# Zio_Qwiic_LoRa_Module_915MHZ.net
KiCad netlist of a schematic drawn in EAGLE
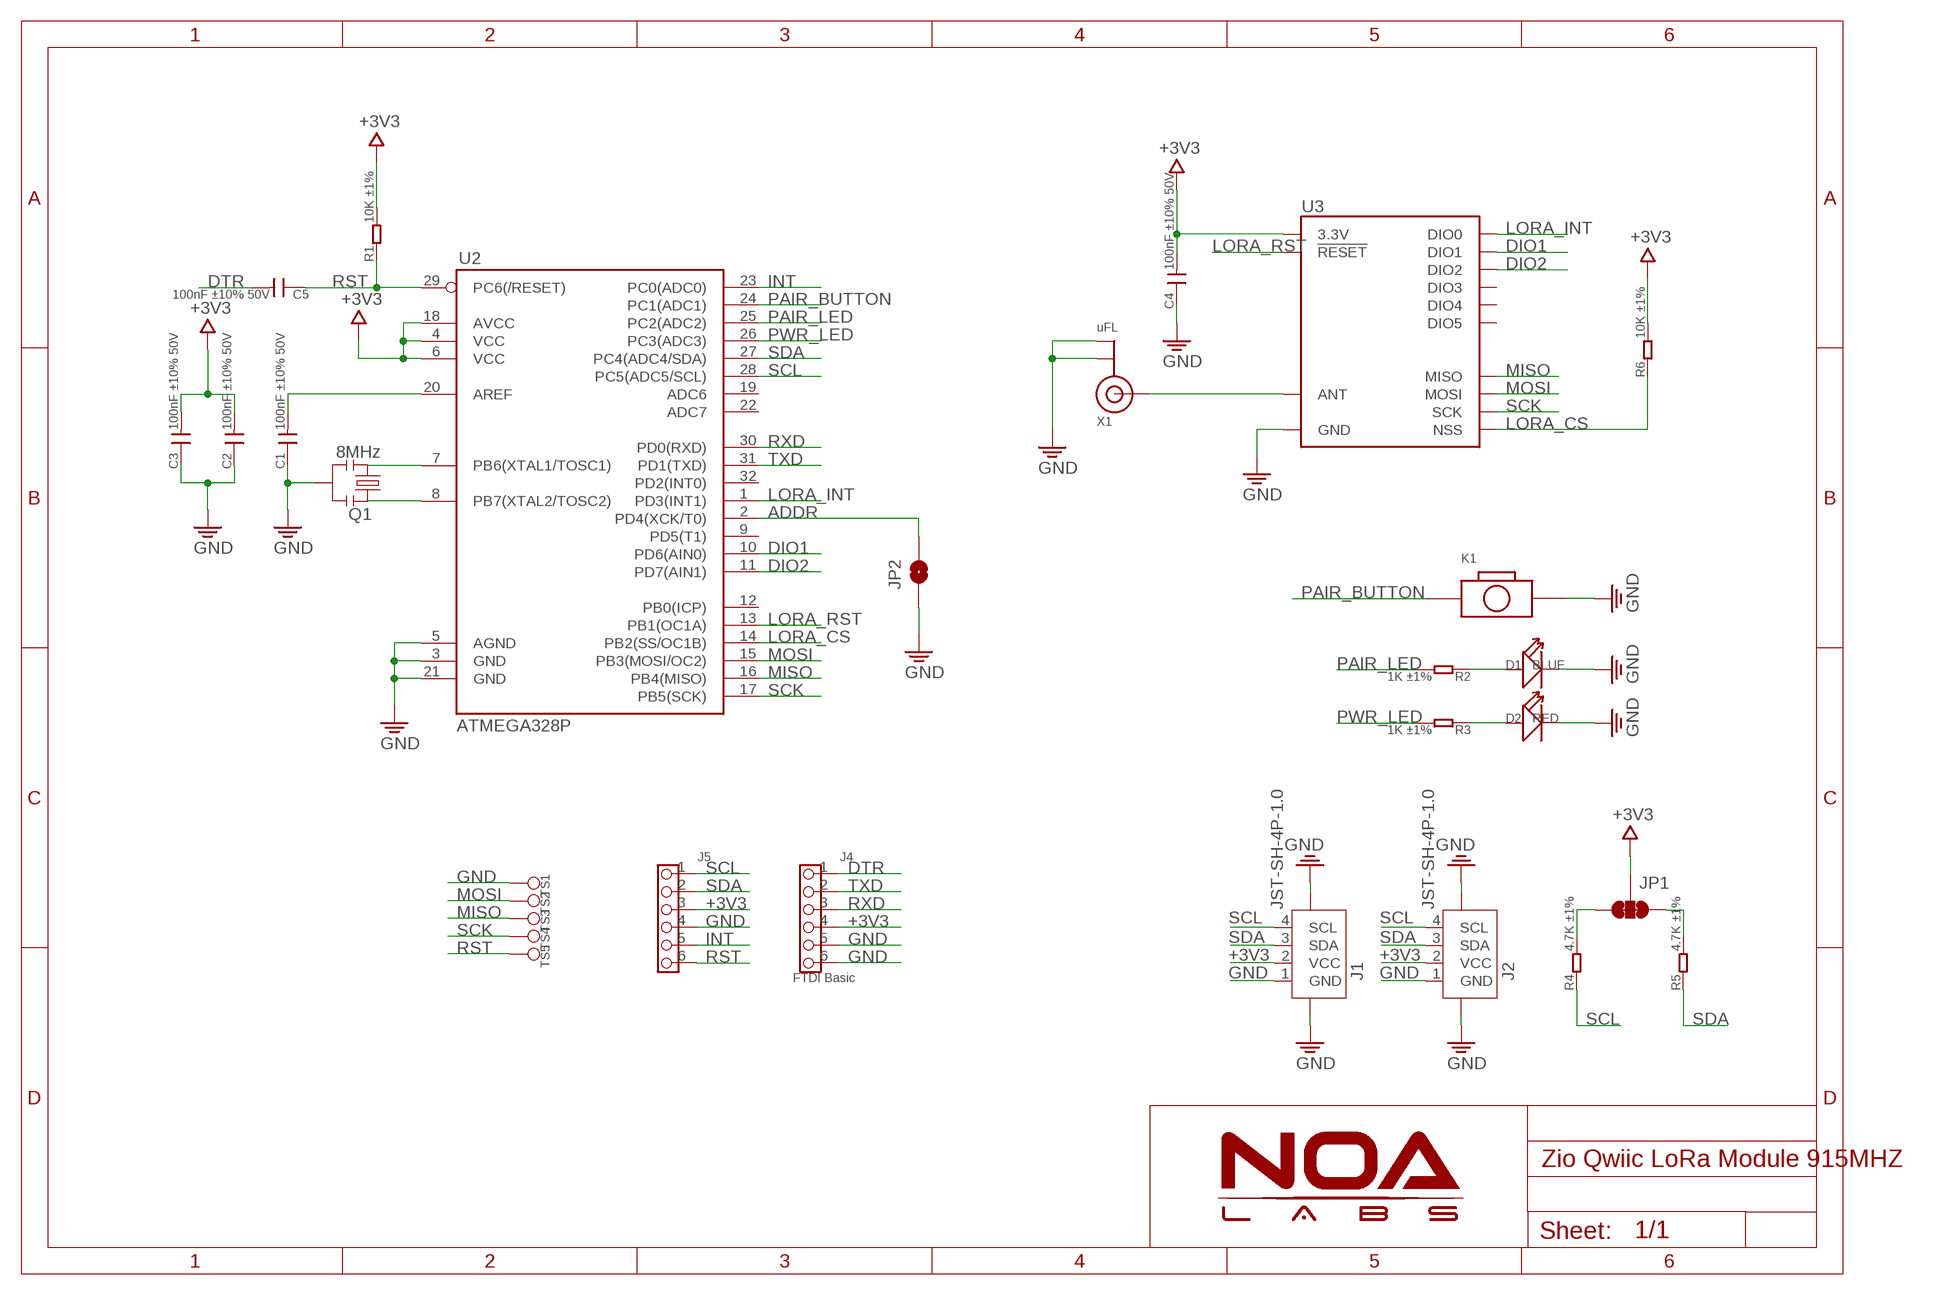
[diagram p0: schematic, sheet 1]

(export (version "E")
  (design (tool "Eeschema 10.0.6"))
  (components
    (comp (ref "C1")
      (value "100nF ±10% 50V")
      (footprint "eagle-import:C0603")
      (libsource (lib "eagle-import") (part "C-0603"))
    )
    (comp (ref "C2")
      (value "100nF ±10% 50V")
      (footprint "eagle-import:C0603")
      (libsource (lib "eagle-import") (part "C-0603"))
    )
    (comp (ref "C3")
      (value "100nF ±10% 50V")
      (footprint "eagle-import:C0603")
      (libsource (lib "eagle-import") (part "C-0603"))
    )
    (comp (ref "C4")
      (value "100nF ±10% 50V")
      (footprint "eagle-import:C0603")
      (libsource (lib "eagle-import") (part "C-0603"))
    )
    (comp (ref "C5")
      (value "100nF ±10% 50V")
      (footprint "eagle-import:C0603")
      (libsource (lib "eagle-import") (part "C-0603"))
    )
    (comp (ref "D1")
      (value "BLUE")
      (footprint "eagle-import:LED-0603")
      (libsource (lib "eagle-import") (part "LED'0603'"))
    )
    (comp (ref "D2")
      (value "RED")
      (footprint "eagle-import:LED-0603")
      (libsource (lib "eagle-import") (part "LED'0603'"))
    )
    (comp (ref "J1")
      (value "JST-SH-4P-1.0")
      (footprint "eagle-import:JST-SH-4P")
      (libsource (lib "eagle-import") (part "JST-SH-4P-1.0"))
    )
    (comp (ref "J2")
      (value "JST-SH-4P-1.0")
      (footprint "eagle-import:JST-SH-4P")
      (libsource (lib "eagle-import") (part "JST-SH-4P-1.0"))
    )
    (comp (ref "J4")
      (value "FTDI Basic")
      (footprint "eagle-import:6P-2.54-60_35MIL")
      (libsource (lib "eagle-import") (part "HEADER-6P-60/35MIL"))
    )
    (comp (ref "J5")
      (value "HEADER-6P-60/35MIL")
      (footprint "eagle-import:6P-2.54-60_35MIL")
      (libsource (lib "eagle-import") (part "HEADER-6P-60/35MIL"))
    )
    (comp (ref "JP1")
      (value "SMT-JUMPER_3_2-NC_TRACE")
      (footprint "eagle-import:SMT-JUMPER_3_2-NC_TRACE")
      (libsource (lib "eagle-import") (part "SMT-JUMPER_3_2-NC_TRACE"))
    )
    (comp (ref "JP2")
      (value "JUMPER-SMT_2_NC_PASTE_NOCREM")
      (footprint "eagle-import:SMT-JUMPER_2_NC_PASTE_SILK_NOCREM")
      (libsource (lib "eagle-import") (part "JUMPER-SMT_2_NC_PASTE_NOCREM"))
    )
    (comp (ref "K1")
      (value "BOTTON-2PSKRKAEE020")
      (footprint "eagle-import:SKRKAEE020")
      (libsource (lib "eagle-import") (part "BOTTON-2PSKRKAEE020"))
    )
    (comp (ref "Q1")
      (value "8MHz")
      (footprint "eagle-import:RESONATOR-SMD")
      (libsource (lib "eagle-import") (part "RESONATORSMD"))
    )
    (comp (ref "R1")
      (value "10K ±1%")
      (footprint "eagle-import:R0603")
      (libsource (lib "eagle-import") (part "R-0603"))
    )
    (comp (ref "R2")
      (value "1K ±1%")
      (footprint "eagle-import:R0603")
      (libsource (lib "eagle-import") (part "R-0603"))
    )
    (comp (ref "R3")
      (value "1K ±1%")
      (footprint "eagle-import:R0603")
      (libsource (lib "eagle-import") (part "R-0603"))
    )
    (comp (ref "R4")
      (value "4.7K ±1%")
      (footprint "eagle-import:R0603")
      (libsource (lib "eagle-import") (part "R-0603"))
    )
    (comp (ref "R5")
      (value "4.7K ±1%")
      (footprint "eagle-import:R0603")
      (libsource (lib "eagle-import") (part "R-0603"))
    )
    (comp (ref "R6")
      (value "10K ±1%")
      (footprint "eagle-import:R0603")
      (libsource (lib "eagle-import") (part "R-0603"))
    )
    (comp (ref "TS1")
      (value "TEST_POINT35MIL")
      (footprint "eagle-import:1P-35MIL")
      (libsource (lib "eagle-import") (part "TEST_POINT35MIL"))
    )
    (comp (ref "TS2")
      (value "TEST_POINT35MIL")
      (footprint "eagle-import:1P-35MIL")
      (libsource (lib "eagle-import") (part "TEST_POINT35MIL"))
    )
    (comp (ref "TS3")
      (value "TEST_POINT35MIL")
      (footprint "eagle-import:1P-35MIL")
      (libsource (lib "eagle-import") (part "TEST_POINT35MIL"))
    )
    (comp (ref "TS4")
      (value "TEST_POINT35MIL")
      (footprint "eagle-import:1P-35MIL")
      (libsource (lib "eagle-import") (part "TEST_POINT35MIL"))
    )
    (comp (ref "TS5")
      (value "TEST_POINT35MIL")
      (footprint "eagle-import:1P-35MIL")
      (libsource (lib "eagle-import") (part "TEST_POINT35MIL"))
    )
    (comp (ref "U2")
      (value "ATMEGA328P")
      (footprint "eagle-import:TQFP32-08")
      (libsource (lib "eagle-import") (part "ATMEGA168"))
    )
    (comp (ref "U3")
      (value "SPARKX_RFM96W")
      (footprint "eagle-import:SPARKX_RFM95_96_97_98W")
      (libsource (lib "eagle-import") (part "SPARKX_RFM96W"))
    )
    (comp (ref "X1")
      (value "uFL")
      (footprint "eagle-import:U.FL")
      (libsource (lib "eagle-import") (part "ANTENNA_U.FL"))
    )
  )
  (nets
    (net (code "1") (name "+3V3") (class "Default")
      (node (ref "C2") (pin "2") (pinfunction "2_2") (pintype "passive"))
      (node (ref "C3") (pin "2") (pinfunction "2_2") (pintype "passive"))
      (node (ref "C4") (pin "2") (pinfunction "2_2") (pintype "passive"))
      (node (ref "J1") (pin "2") (pinfunction "VCC_2") (pintype "bidirectional"))
      (node (ref "J2") (pin "2") (pinfunction "VCC_2") (pintype "bidirectional"))
      (node (ref "J4") (pin "4") (pinfunction "4_4") (pintype "bidirectional"))
      (node (ref "J5") (pin "3") (pinfunction "3_3") (pintype "bidirectional"))
      (node (ref "JP1") (pin "2") (pinfunction "2_2") (pintype "passive"))
      (node (ref "R1") (pin "2") (pinfunction "2_2") (pintype "passive"))
      (node (ref "R6") (pin "2") (pinfunction "2_2") (pintype "passive"))
      (node (ref "U2") (pin "18") (pinfunction "AVCC_18") (pintype "bidirectional"))
      (node (ref "U2") (pin "4") (pinfunction "VCC_4") (pintype "bidirectional"))
      (node (ref "U2") (pin "6") (pinfunction "VCC_6") (pintype "bidirectional"))
      (node (ref "U3") (pin "3.3V") (pinfunction "3.3V_3.3V") (pintype "bidirectional"))
    )
    (net (code "2") (name "/ADDR") (class "Default")
      (node (ref "JP2") (pin "2") (pinfunction "2_2") (pintype "passive"))
      (node (ref "U2") (pin "2") (pinfunction "PD4(XCK/T0)_2") (pintype "bidirectional"))
    )
    (net (code "3") (name "/DIO1") (class "Default")
      (node (ref "U2") (pin "10") (pinfunction "PD6(AIN0)_10") (pintype "bidirectional"))
      (node (ref "U3") (pin "DIO1") (pinfunction "DIO1_DIO1") (pintype "bidirectional"))
    )
    (net (code "4") (name "/DIO2") (class "Default")
      (node (ref "U2") (pin "11") (pinfunction "PD7(AIN1)_11") (pintype "bidirectional"))
      (node (ref "U3") (pin "DIO2") (pinfunction "DIO2_DIO2") (pintype "bidirectional"))
    )
    (net (code "5") (name "/DTR") (class "Default")
      (node (ref "C5") (pin "2") (pinfunction "2_2") (pintype "passive"))
      (node (ref "J4") (pin "1") (pinfunction "1_1") (pintype "bidirectional"))
    )
    (net (code "6") (name "/INT") (class "Default")
      (node (ref "J5") (pin "5") (pinfunction "5_5") (pintype "bidirectional"))
      (node (ref "U2") (pin "23") (pinfunction "PC0(ADC0)_23") (pintype "bidirectional"))
    )
    (net (code "7") (name "/LORA_CS") (class "Default")
      (node (ref "R6") (pin "1") (pinfunction "1_1") (pintype "passive"))
      (node (ref "U2") (pin "14") (pinfunction "PB2(SS/OC1B)_14") (pintype "bidirectional"))
      (node (ref "U3") (pin "NSS") (pinfunction "NSS_NSS") (pintype "bidirectional"))
    )
    (net (code "8") (name "/LORA_INT") (class "Default")
      (node (ref "U2") (pin "1") (pinfunction "PD3(INT1)_1") (pintype "bidirectional"))
      (node (ref "U3") (pin "DIO0") (pinfunction "DIO0_DIO0") (pintype "bidirectional"))
    )
    (net (code "9") (name "/LORA_RST") (class "Default")
      (node (ref "U2") (pin "13") (pinfunction "PB1(OC1A)_13") (pintype "bidirectional"))
      (node (ref "U3") (pin "!RESET") (pinfunction "~{RESET}_!RESET") (pintype "bidirectional"))
    )
    (net (code "10") (name "/MISO") (class "Default")
      (node (ref "TS3") (pin "P$1") (pinfunction "1_P$1") (pintype "bidirectional"))
      (node (ref "U2") (pin "16") (pinfunction "PB4(MISO)_16") (pintype "bidirectional"))
      (node (ref "U3") (pin "MISO") (pinfunction "MISO_MISO") (pintype "bidirectional"))
    )
    (net (code "11") (name "/MOSI") (class "Default")
      (node (ref "TS2") (pin "P$1") (pinfunction "1_P$1") (pintype "bidirectional"))
      (node (ref "U2") (pin "15") (pinfunction "PB3(MOSI/OC2)_15") (pintype "bidirectional"))
      (node (ref "U3") (pin "MOSI") (pinfunction "MOSI_MOSI") (pintype "bidirectional"))
    )
    (net (code "12") (name "/PAIR_BUTTON") (class "Default")
      (node (ref "K1") (pin "1") (pinfunction "1_1") (pintype "bidirectional"))
      (node (ref "U2") (pin "24") (pinfunction "PC1(ADC1)_24") (pintype "bidirectional"))
    )
    (net (code "13") (name "/PAIR_LED") (class "Default")
      (node (ref "R2") (pin "2") (pinfunction "2_2") (pintype "passive"))
      (node (ref "U2") (pin "25") (pinfunction "PC2(ADC2)_25") (pintype "bidirectional"))
    )
    (net (code "14") (name "/PWR_LED") (class "Default")
      (node (ref "R3") (pin "2") (pinfunction "2_2") (pintype "passive"))
      (node (ref "U2") (pin "26") (pinfunction "PC3(ADC3)_26") (pintype "bidirectional"))
    )
    (net (code "15") (name "/RST") (class "Default")
      (node (ref "C5") (pin "1") (pinfunction "1_1") (pintype "passive"))
      (node (ref "J5") (pin "6") (pinfunction "6_6") (pintype "bidirectional"))
      (node (ref "R1") (pin "1") (pinfunction "1_1") (pintype "passive"))
      (node (ref "TS5") (pin "P$1") (pinfunction "1_P$1") (pintype "bidirectional"))
      (node (ref "U2") (pin "29") (pinfunction "PC6(/RESET)_29") (pintype "bidirectional"))
    )
    (net (code "16") (name "/RXD") (class "Default")
      (node (ref "J4") (pin "3") (pinfunction "3_3") (pintype "bidirectional"))
      (node (ref "U2") (pin "30") (pinfunction "PD0(RXD)_30") (pintype "bidirectional"))
    )
    (net (code "17") (name "/SCK") (class "Default")
      (node (ref "TS4") (pin "P$1") (pinfunction "1_P$1") (pintype "bidirectional"))
      (node (ref "U2") (pin "17") (pinfunction "PB5(SCK)_17") (pintype "bidirectional"))
      (node (ref "U3") (pin "SCK") (pinfunction "SCK_SCK") (pintype "bidirectional"))
    )
    (net (code "18") (name "/SCL") (class "Default")
      (node (ref "J1") (pin "4") (pinfunction "SCL_4") (pintype "bidirectional"))
      (node (ref "J2") (pin "4") (pinfunction "SCL_4") (pintype "bidirectional"))
      (node (ref "J5") (pin "1") (pinfunction "1_1") (pintype "bidirectional"))
      (node (ref "R4") (pin "1") (pinfunction "1_1") (pintype "passive"))
      (node (ref "U2") (pin "28") (pinfunction "PC5(ADC5/SCL)_28") (pintype "bidirectional"))
    )
    (net (code "19") (name "/SDA") (class "Default")
      (node (ref "J1") (pin "3") (pinfunction "SDA_3") (pintype "bidirectional"))
      (node (ref "J2") (pin "3") (pinfunction "SDA_3") (pintype "bidirectional"))
      (node (ref "J5") (pin "2") (pinfunction "2_2") (pintype "bidirectional"))
      (node (ref "R5") (pin "1") (pinfunction "1_1") (pintype "passive"))
      (node (ref "U2") (pin "27") (pinfunction "PC4(ADC4/SDA)_27") (pintype "bidirectional"))
    )
    (net (code "20") (name "/TXD") (class "Default")
      (node (ref "J4") (pin "2") (pinfunction "2_2") (pintype "bidirectional"))
      (node (ref "U2") (pin "31") (pinfunction "PD1(TXD)_31") (pintype "bidirectional"))
    )
    (net (code "21") (name "GND") (class "Default")
      (node (ref "C1") (pin "1") (pinfunction "1_1") (pintype "passive"))
      (node (ref "C2") (pin "1") (pinfunction "1_1") (pintype "passive"))
      (node (ref "C3") (pin "1") (pinfunction "1_1") (pintype "passive"))
      (node (ref "C4") (pin "1") (pinfunction "1_1") (pintype "passive"))
      (node (ref "D1") (pin "-") (pinfunction "-_-") (pintype "passive"))
      (node (ref "D2") (pin "-") (pinfunction "-_-") (pintype "passive"))
      (node (ref "J1") (pin "1") (pinfunction "GND_1") (pintype "bidirectional"))
      (node (ref "J1") (pin "NC1") (pinfunction "5_NC1") (pintype "bidirectional"))
      (node (ref "J1") (pin "NC2") (pinfunction "6_NC2") (pintype "bidirectional"))
      (node (ref "J2") (pin "1") (pinfunction "GND_1") (pintype "bidirectional"))
      (node (ref "J2") (pin "NC1") (pinfunction "5_NC1") (pintype "bidirectional"))
      (node (ref "J2") (pin "NC2") (pinfunction "6_NC2") (pintype "bidirectional"))
      (node (ref "J4") (pin "5") (pinfunction "5_5") (pintype "bidirectional"))
      (node (ref "J4") (pin "6") (pinfunction "6_6") (pintype "bidirectional"))
      (node (ref "J5") (pin "4") (pinfunction "4_4") (pintype "bidirectional"))
      (node (ref "JP2") (pin "1") (pinfunction "1_1") (pintype "passive"))
      (node (ref "K1") (pin "2") (pinfunction "2_2") (pintype "bidirectional"))
      (node (ref "Q1") (pin "2") (pinfunction "2_2") (pintype "passive"))
      (node (ref "TS1") (pin "P$1") (pinfunction "1_P$1") (pintype "bidirectional"))
      (node (ref "U2") (pin "21") (pinfunction "GND_21") (pintype "bidirectional"))
      (node (ref "U2") (pin "3") (pinfunction "GND_3") (pintype "bidirectional"))
      (node (ref "U2") (pin "5") (pinfunction "AGND_5") (pintype "bidirectional"))
      (node (ref "U3") (pin "GND@1") (pinfunction "GND_GND@1") (pintype "bidirectional"))
      (node (ref "U3") (pin "GND@2") (pinfunction "GND_GND@2") (pintype "bidirectional"))
      (node (ref "U3") (pin "GND@3") (pinfunction "GND_GND@3") (pintype "bidirectional"))
      (node (ref "X1") (pin "1") (pinfunction "GND_1") (pintype "passive"))
      (node (ref "X1") (pin "2") (pinfunction "GND_2") (pintype "passive"))
    )
    (net (code "22") (name "Net-(D1-Pad+)") (class "Default")
      (node (ref "D1") (pin "+") (pinfunction "+_+") (pintype "passive"))
      (node (ref "R2") (pin "1") (pinfunction "1_1") (pintype "passive"))
    )
    (net (code "23") (name "Net-(D2-Pad+)") (class "Default")
      (node (ref "D2") (pin "+") (pinfunction "+_+") (pintype "passive"))
      (node (ref "R3") (pin "1") (pinfunction "1_1") (pintype "passive"))
    )
    (net (code "24") (name "Net-(JP1-Pad1)") (class "Default")
      (node (ref "JP1") (pin "1") (pinfunction "1_1") (pintype "passive"))
      (node (ref "R5") (pin "2") (pinfunction "2_2") (pintype "passive"))
    )
    (net (code "25") (name "Net-(JP1-Pad3)") (class "Default")
      (node (ref "JP1") (pin "3") (pinfunction "3_3") (pintype "passive"))
      (node (ref "R4") (pin "2") (pinfunction "2_2") (pintype "passive"))
    )
    (net (code "26") (name "Net-(U2-AREF)") (class "Default")
      (node (ref "C1") (pin "2") (pinfunction "2_2") (pintype "passive"))
      (node (ref "U2") (pin "20") (pinfunction "AREF_20") (pintype "bidirectional"))
    )
    (net (code "27") (name "Net-(U2-PB6(XTAL1{slash}TOSC1))") (class "Default")
      (node (ref "Q1") (pin "3") (pinfunction "3_3") (pintype "passive"))
      (node (ref "U2") (pin "7") (pinfunction "PB6(XTAL1/TOSC1)_7") (pintype "bidirectional"))
    )
    (net (code "28") (name "Net-(U2-PB7(XTAL2{slash}TOSC2))") (class "Default")
      (node (ref "Q1") (pin "1") (pinfunction "1_1") (pintype "passive"))
      (node (ref "U2") (pin "8") (pinfunction "PB7(XTAL2/TOSC2)_8") (pintype "bidirectional"))
    )
    (net (code "29") (name "Net-(X1-SIGNAL)") (class "Default")
      (node (ref "U3") (pin "ANT") (pinfunction "ANT_ANT") (pintype "bidirectional"))
      (node (ref "X1") (pin "3") (pinfunction "SIGNAL_3") (pintype "passive"))
    )
    (net (code "30") (name "unconnected-(U2-ADC6-Pad19)") (class "Default")
      (node (ref "U2") (pin "19") (pinfunction "ADC6_19") (pintype "bidirectional"))
    )
    (net (code "31") (name "unconnected-(U2-ADC7-Pad22)") (class "Default")
      (node (ref "U2") (pin "22") (pinfunction "ADC7_22") (pintype "bidirectional"))
    )
    (net (code "32") (name "unconnected-(U2-PB0(ICP)-Pad12)") (class "Default")
      (node (ref "U2") (pin "12") (pinfunction "PB0(ICP)_12") (pintype "bidirectional"))
    )
    (net (code "33") (name "unconnected-(U2-PD2(INT0)-Pad32)") (class "Default")
      (node (ref "U2") (pin "32") (pinfunction "PD2(INT0)_32") (pintype "bidirectional"))
    )
    (net (code "34") (name "unconnected-(U2-PD5(T1)-Pad9)") (class "Default")
      (node (ref "U2") (pin "9") (pinfunction "PD5(T1)_9") (pintype "bidirectional"))
    )
    (net (code "35") (name "unconnected-(U3-PadDIO3)") (class "Default")
      (node (ref "U3") (pin "DIO3") (pinfunction "DIO3_DIO3") (pintype "bidirectional"))
    )
    (net (code "36") (name "unconnected-(U3-PadDIO4)") (class "Default")
      (node (ref "U3") (pin "DIO4") (pinfunction "DIO4_DIO4") (pintype "bidirectional"))
    )
    (net (code "37") (name "unconnected-(U3-PadDIO5)") (class "Default")
      (node (ref "U3") (pin "DIO5") (pinfunction "DIO5_DIO5") (pintype "bidirectional"))
    )
  )
)
